# S7CAS-PLEIADES-CARTE-MERE_Pxx_DDR.net
KiCad netlist of a schematic drawn in Altium Designer
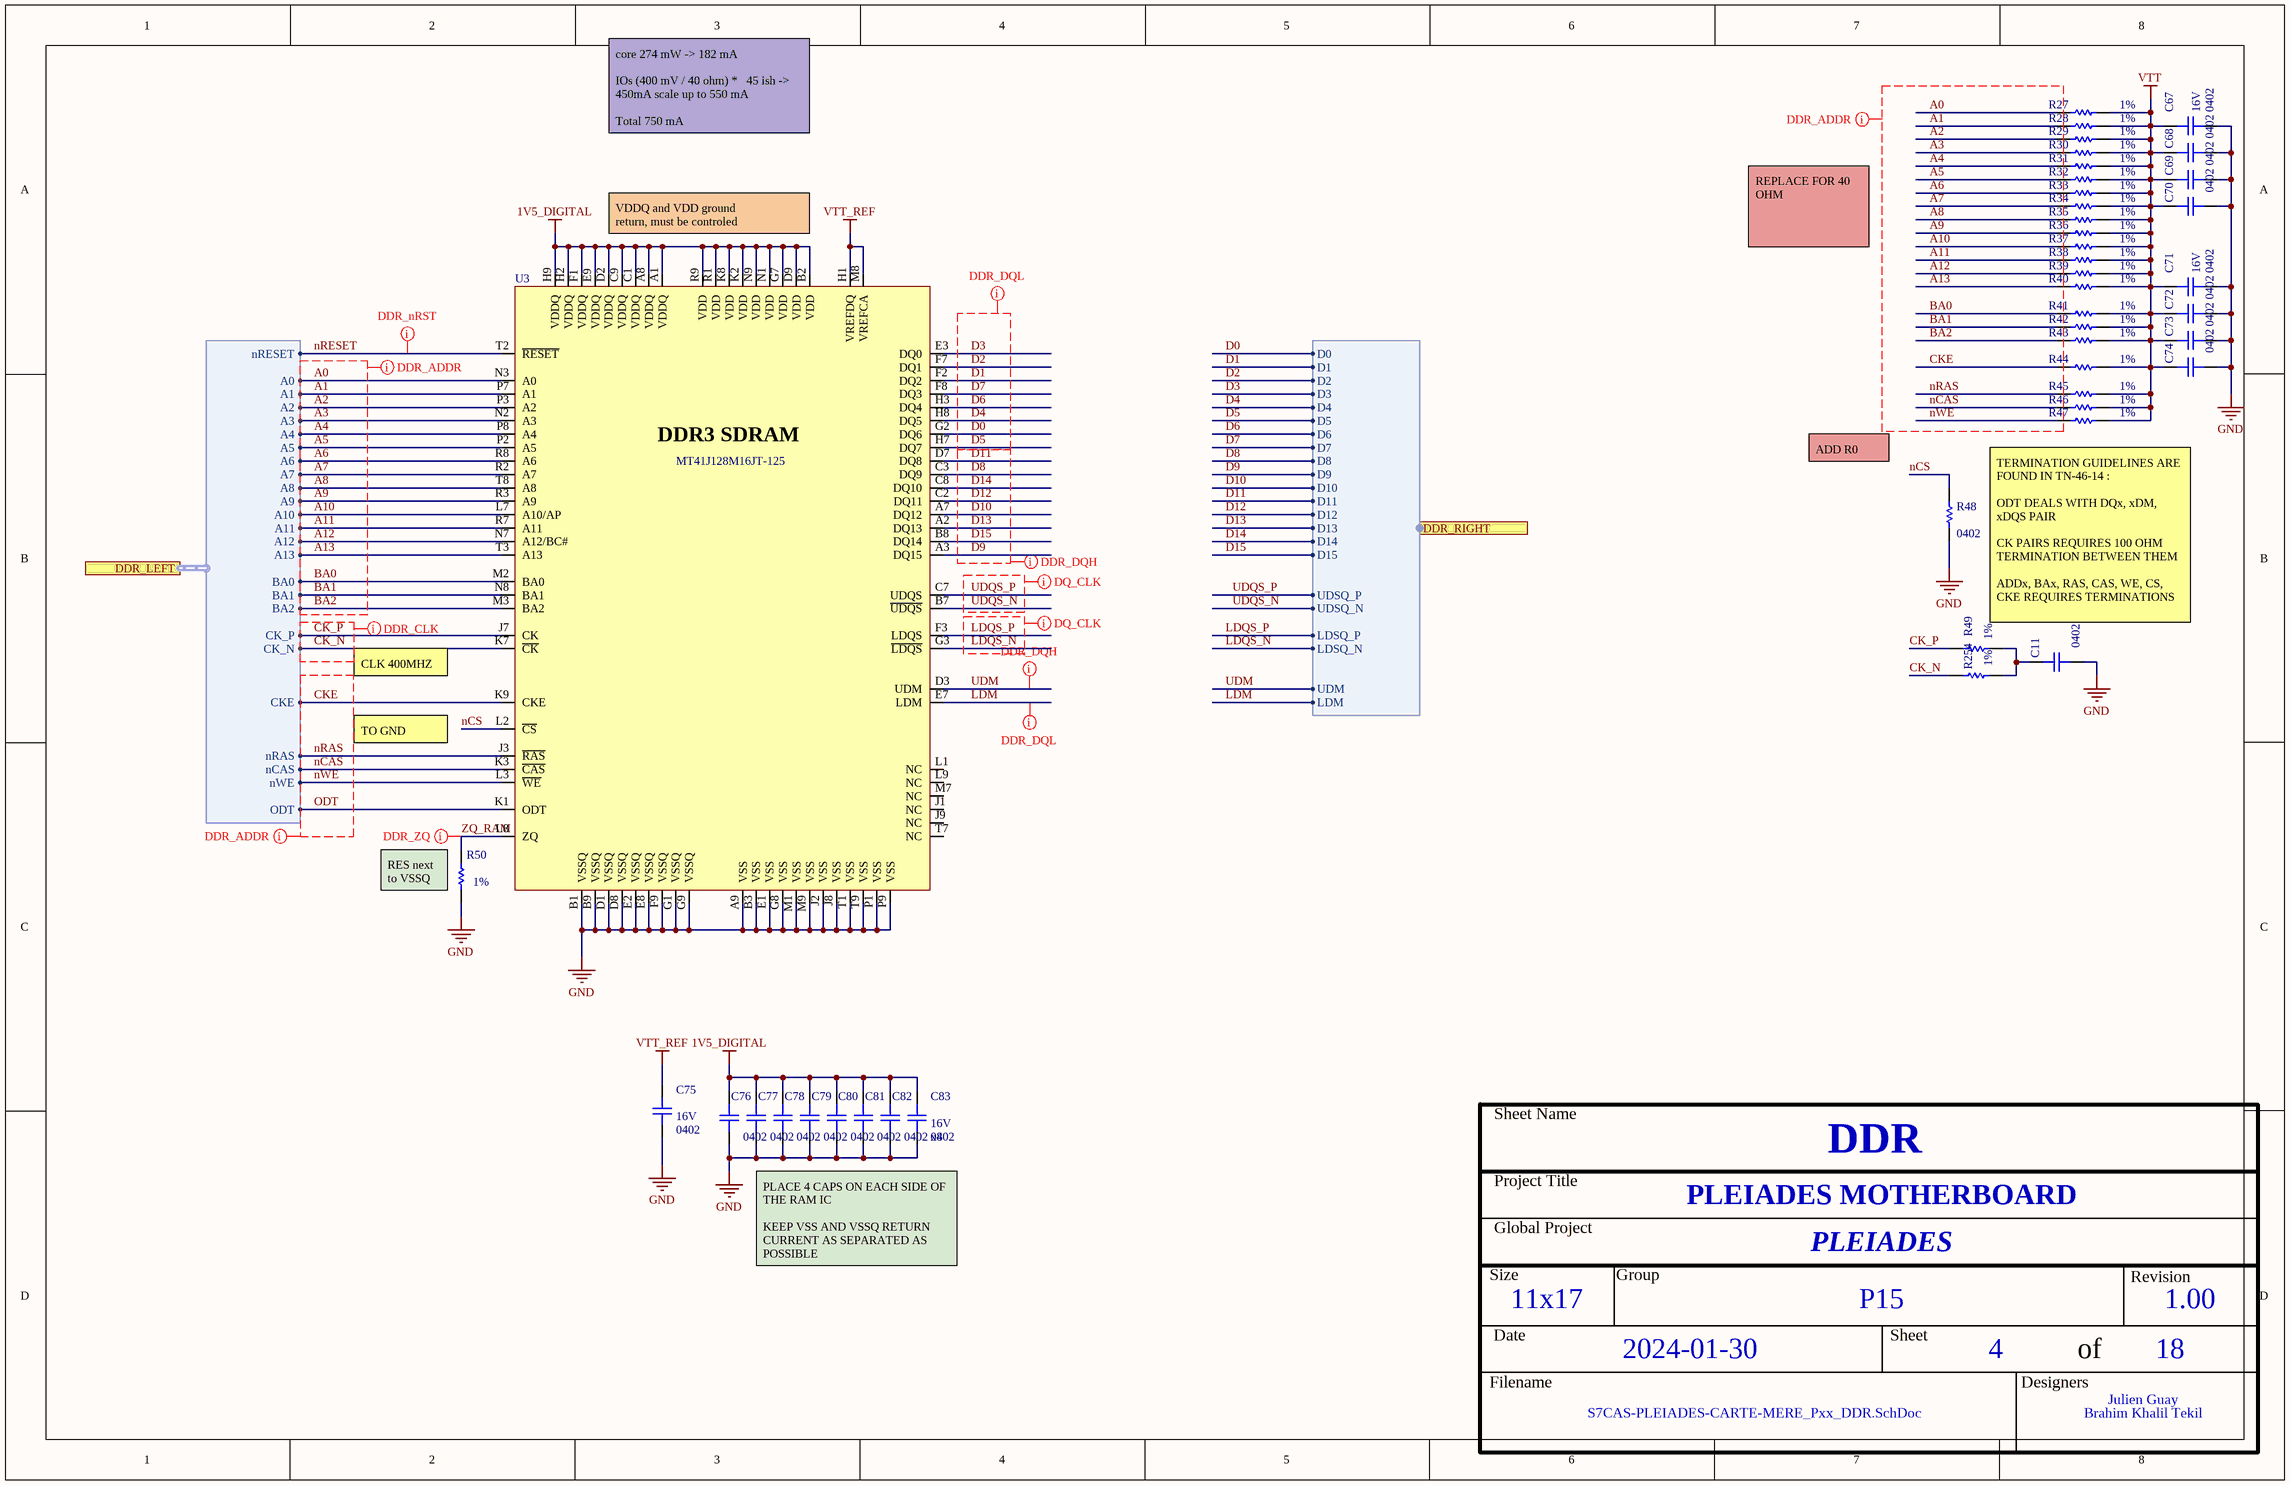
[diagram p0: S7CAS-PLEIADES-CARTE-MERE_Pxx_DDR.SchDoc]

(export (version "E")
  (design (tool "Eeschema 10.0.6"))
  (components
    (comp (ref "C11")
      (value "0402")
      (footprint "S7CAS_LIB2023:CAP_0402")
      (description "CAP - 0402")
      (fields
        (field (name "VOLTAGE") "16V")
        (field (name "PACKAGE") "0402")
        (field (name "CREATEDBY") "Jonathan Bouchard")
      )
      (libsource (lib "S7CAS_LIB2023") (part "CAP - 0603"))
    )
    (comp (ref "C67")
      (value "0402")
      (footprint "S7CAS_LIB2023:CAP_0402")
      (description "CAP - 0402")
      (fields
        (field (name "VOLTAGE") "16V")
        (field (name "PACKAGE") "0402")
        (field (name "CREATEDBY") "Jonathan Bouchard")
      )
      (libsource (lib "S7CAS_LIB2023") (part "CAP - 0603"))
    )
    (comp (ref "C68")
      (value "0402")
      (footprint "S7CAS_LIB2023:CAP_0402")
      (description "CAP - 0402")
      (fields
        (field (name "VOLTAGE") "16V")
        (field (name "PACKAGE") "0402")
        (field (name "CREATEDBY") "Jonathan Bouchard")
      )
      (libsource (lib "S7CAS_LIB2023") (part "CAP - 0603"))
    )
    (comp (ref "C69")
      (value "0402")
      (footprint "S7CAS_LIB2023:CAP_0402")
      (description "CAP - 0402")
      (fields
        (field (name "VOLTAGE") "16V")
        (field (name "PACKAGE") "0402")
        (field (name "CREATEDBY") "Jonathan Bouchard")
      )
      (libsource (lib "S7CAS_LIB2023") (part "CAP - 0603"))
    )
    (comp (ref "C70")
      (value "0402")
      (footprint "S7CAS_LIB2023:CAP_0402")
      (description "CAP - 0402")
      (fields
        (field (name "VOLTAGE") "16V")
        (field (name "PACKAGE") "0402")
        (field (name "CREATEDBY") "Jonathan Bouchard")
      )
      (libsource (lib "S7CAS_LIB2023") (part "CAP - 0603"))
    )
    (comp (ref "C71")
      (value "0402")
      (footprint "S7CAS_LIB2023:CAP_0402")
      (description "CAP - 0402")
      (fields
        (field (name "VOLTAGE") "16V")
        (field (name "PACKAGE") "0402")
        (field (name "CREATEDBY") "Jonathan Bouchard")
      )
      (libsource (lib "S7CAS_LIB2023") (part "CAP - 0603"))
    )
    (comp (ref "C72")
      (value "0402")
      (footprint "S7CAS_LIB2023:CAP_0402")
      (description "CAP - 0402")
      (fields
        (field (name "VOLTAGE") "16V")
        (field (name "PACKAGE") "0402")
        (field (name "CREATEDBY") "Jonathan Bouchard")
      )
      (libsource (lib "S7CAS_LIB2023") (part "CAP - 0603"))
    )
    (comp (ref "C73")
      (value "0402")
      (footprint "S7CAS_LIB2023:CAP_0402")
      (description "CAP - 0402")
      (fields
        (field (name "VOLTAGE") "16V")
        (field (name "PACKAGE") "0402")
        (field (name "CREATEDBY") "Jonathan Bouchard")
      )
      (libsource (lib "S7CAS_LIB2023") (part "CAP - 0603"))
    )
    (comp (ref "C74")
      (value "0402")
      (footprint "S7CAS_LIB2023:CAP_0402")
      (description "CAP - 0402")
      (fields
        (field (name "VOLTAGE") "16V")
        (field (name "PACKAGE") "0402")
        (field (name "CREATEDBY") "Jonathan Bouchard")
      )
      (libsource (lib "S7CAS_LIB2023") (part "CAP - 0603"))
    )
    (comp (ref "C75")
      (value "0402")
      (footprint "S7CAS_LIB2023:CAP_0402")
      (description "CAP - 0402")
      (fields
        (field (name "VOLTAGE") "16V")
        (field (name "PACKAGE") "0402")
        (field (name "CREATEDBY") "Jonathan Bouchard")
      )
      (libsource (lib "S7CAS_LIB2023") (part "CAP - 0603"))
    )
    (comp (ref "C76")
      (value "0402")
      (footprint "S7CAS_LIB2023:CAP_0402")
      (description "CAP - 0402")
      (fields
        (field (name "VOLTAGE") "16V")
        (field (name "PACKAGE") "0402")
        (field (name "CREATEDBY") "Jonathan Bouchard")
      )
      (libsource (lib "S7CAS_LIB2023") (part "CAP - 0603"))
    )
    (comp (ref "C77")
      (value "0402")
      (footprint "S7CAS_LIB2023:CAP_0402")
      (description "CAP - 0402")
      (fields
        (field (name "VOLTAGE") "16V")
        (field (name "PACKAGE") "0402")
        (field (name "CREATEDBY") "Jonathan Bouchard")
      )
      (libsource (lib "S7CAS_LIB2023") (part "CAP - 0603"))
    )
    (comp (ref "C78")
      (value "0402")
      (footprint "S7CAS_LIB2023:CAP_0402")
      (description "CAP - 0402")
      (fields
        (field (name "VOLTAGE") "16V")
        (field (name "PACKAGE") "0402")
        (field (name "CREATEDBY") "Jonathan Bouchard")
      )
      (libsource (lib "S7CAS_LIB2023") (part "CAP - 0603"))
    )
    (comp (ref "C79")
      (value "0402")
      (footprint "S7CAS_LIB2023:CAP_0402")
      (description "CAP - 0402")
      (fields
        (field (name "VOLTAGE") "16V")
        (field (name "PACKAGE") "0402")
        (field (name "CREATEDBY") "Jonathan Bouchard")
      )
      (libsource (lib "S7CAS_LIB2023") (part "CAP - 0603"))
    )
    (comp (ref "C80")
      (value "0402")
      (footprint "S7CAS_LIB2023:CAP_0402")
      (description "CAP - 0402")
      (fields
        (field (name "VOLTAGE") "16V")
        (field (name "PACKAGE") "0402")
        (field (name "CREATEDBY") "Jonathan Bouchard")
      )
      (libsource (lib "S7CAS_LIB2023") (part "CAP - 0603"))
    )
    (comp (ref "C81")
      (value "0402")
      (footprint "S7CAS_LIB2023:CAP_0402")
      (description "CAP - 0402")
      (fields
        (field (name "VOLTAGE") "16V")
        (field (name "PACKAGE") "0402")
        (field (name "CREATEDBY") "Jonathan Bouchard")
      )
      (libsource (lib "S7CAS_LIB2023") (part "CAP - 0603"))
    )
    (comp (ref "C82")
      (value "0402")
      (footprint "S7CAS_LIB2023:CAP_0402")
      (description "CAP - 0402")
      (fields
        (field (name "VOLTAGE") "16V")
        (field (name "PACKAGE") "0402")
        (field (name "CREATEDBY") "Jonathan Bouchard")
      )
      (libsource (lib "S7CAS_LIB2023") (part "CAP - 0603"))
    )
    (comp (ref "C83")
      (value "0402")
      (footprint "S7CAS_LIB2023:CAP_0402")
      (description "CAP - 0402")
      (fields
        (field (name "VOLTAGE") "16V")
        (field (name "PACKAGE") "0402")
        (field (name "CREATEDBY") "Jonathan Bouchard")
      )
      (libsource (lib "S7CAS_LIB2023") (part "CAP - 0603"))
    )
    (comp (ref "R27")
      (value "RES - 0603")
      (footprint "S7CAS_LIB2023:RES_0402")
      (description "RES - 0402")
      (fields (field (name "PRECISION") "1%") (field (name "CREATEDBY") "Jonathan Bouchard"))
      (libsource (lib "S7CAS_LIB2023") (part "RES - 0603"))
    )
    (comp (ref "R28")
      (value "RES - 0603")
      (footprint "S7CAS_LIB2023:RES_0402")
      (description "RES - 0402")
      (fields (field (name "PRECISION") "1%") (field (name "CREATEDBY") "Jonathan Bouchard"))
      (libsource (lib "S7CAS_LIB2023") (part "RES - 0603"))
    )
    (comp (ref "R29")
      (value "RES - 0603")
      (footprint "S7CAS_LIB2023:RES_0402")
      (description "RES - 0402")
      (fields (field (name "PRECISION") "1%") (field (name "CREATEDBY") "Jonathan Bouchard"))
      (libsource (lib "S7CAS_LIB2023") (part "RES - 0603"))
    )
    (comp (ref "R30")
      (value "RES - 0603")
      (footprint "S7CAS_LIB2023:RES_0402")
      (description "RES - 0402")
      (fields (field (name "PRECISION") "1%") (field (name "CREATEDBY") "Jonathan Bouchard"))
      (libsource (lib "S7CAS_LIB2023") (part "RES - 0603"))
    )
    (comp (ref "R31")
      (value "RES - 0603")
      (footprint "S7CAS_LIB2023:RES_0402")
      (description "RES - 0402")
      (fields (field (name "PRECISION") "1%") (field (name "CREATEDBY") "Jonathan Bouchard"))
      (libsource (lib "S7CAS_LIB2023") (part "RES - 0603"))
    )
    (comp (ref "R32")
      (value "RES - 0603")
      (footprint "S7CAS_LIB2023:RES_0402")
      (description "RES - 0402")
      (fields (field (name "PRECISION") "1%") (field (name "CREATEDBY") "Jonathan Bouchard"))
      (libsource (lib "S7CAS_LIB2023") (part "RES - 0603"))
    )
    (comp (ref "R33")
      (value "RES - 0603")
      (footprint "S7CAS_LIB2023:RES_0402")
      (description "RES - 0402")
      (fields (field (name "PRECISION") "1%") (field (name "CREATEDBY") "Jonathan Bouchard"))
      (libsource (lib "S7CAS_LIB2023") (part "RES - 0603"))
    )
    (comp (ref "R34")
      (value "RES - 0603")
      (footprint "S7CAS_LIB2023:RES_0402")
      (description "RES - 0402")
      (fields (field (name "PRECISION") "1%") (field (name "CREATEDBY") "Jonathan Bouchard"))
      (libsource (lib "S7CAS_LIB2023") (part "RES - 0603"))
    )
    (comp (ref "R35")
      (value "RES - 0603")
      (footprint "S7CAS_LIB2023:RES_0402")
      (description "RES - 0402")
      (fields (field (name "PRECISION") "1%") (field (name "CREATEDBY") "Jonathan Bouchard"))
      (libsource (lib "S7CAS_LIB2023") (part "RES - 0603"))
    )
    (comp (ref "R36")
      (value "RES - 0603")
      (footprint "S7CAS_LIB2023:RES_0402")
      (description "RES - 0402")
      (fields (field (name "PRECISION") "1%") (field (name "CREATEDBY") "Jonathan Bouchard"))
      (libsource (lib "S7CAS_LIB2023") (part "RES - 0603"))
    )
    (comp (ref "R37")
      (value "RES - 0603")
      (footprint "S7CAS_LIB2023:RES_0402")
      (description "RES - 0402")
      (fields (field (name "PRECISION") "1%") (field (name "CREATEDBY") "Jonathan Bouchard"))
      (libsource (lib "S7CAS_LIB2023") (part "RES - 0603"))
    )
    (comp (ref "R38")
      (value "RES - 0603")
      (footprint "S7CAS_LIB2023:RES_0402")
      (description "RES - 0402")
      (fields (field (name "PRECISION") "1%") (field (name "CREATEDBY") "Jonathan Bouchard"))
      (libsource (lib "S7CAS_LIB2023") (part "RES - 0603"))
    )
    (comp (ref "R39")
      (value "RES - 0603")
      (footprint "S7CAS_LIB2023:RES_0402")
      (description "RES - 0402")
      (fields (field (name "PRECISION") "1%") (field (name "CREATEDBY") "Jonathan Bouchard"))
      (libsource (lib "S7CAS_LIB2023") (part "RES - 0603"))
    )
    (comp (ref "R40")
      (value "RES - 0603")
      (footprint "S7CAS_LIB2023:RES_0402")
      (description "RES - 0402")
      (fields (field (name "PRECISION") "1%") (field (name "CREATEDBY") "Jonathan Bouchard"))
      (libsource (lib "S7CAS_LIB2023") (part "RES - 0603"))
    )
    (comp (ref "R41")
      (value "RES - 0603")
      (footprint "S7CAS_LIB2023:RES_0402")
      (description "RES - 0402")
      (fields (field (name "PRECISION") "1%") (field (name "CREATEDBY") "Jonathan Bouchard"))
      (libsource (lib "S7CAS_LIB2023") (part "RES - 0603"))
    )
    (comp (ref "R42")
      (value "RES - 0603")
      (footprint "S7CAS_LIB2023:RES_0402")
      (description "RES - 0402")
      (fields (field (name "PRECISION") "1%") (field (name "CREATEDBY") "Jonathan Bouchard"))
      (libsource (lib "S7CAS_LIB2023") (part "RES - 0603"))
    )
    (comp (ref "R43")
      (value "RES - 0603")
      (footprint "S7CAS_LIB2023:RES_0402")
      (description "RES - 0402")
      (fields (field (name "PRECISION") "1%") (field (name "CREATEDBY") "Jonathan Bouchard"))
      (libsource (lib "S7CAS_LIB2023") (part "RES - 0603"))
    )
    (comp (ref "R44")
      (value "RES - 0603")
      (footprint "S7CAS_LIB2023:RES_0402")
      (description "RES - 0402")
      (fields (field (name "PRECISION") "1%") (field (name "CREATEDBY") "Jonathan Bouchard"))
      (libsource (lib "S7CAS_LIB2023") (part "RES - 0603"))
    )
    (comp (ref "R45")
      (value "RES - 0603")
      (footprint "S7CAS_LIB2023:RES_0402")
      (description "RES - 0402")
      (fields (field (name "PRECISION") "1%") (field (name "CREATEDBY") "Jonathan Bouchard"))
      (libsource (lib "S7CAS_LIB2023") (part "RES - 0603"))
    )
    (comp (ref "R46")
      (value "RES - 0603")
      (footprint "S7CAS_LIB2023:RES_0402")
      (description "RES - 0402")
      (fields (field (name "PRECISION") "1%") (field (name "CREATEDBY") "Jonathan Bouchard"))
      (libsource (lib "S7CAS_LIB2023") (part "RES - 0603"))
    )
    (comp (ref "R47")
      (value "RES - 0603")
      (footprint "S7CAS_LIB2023:RES_0402")
      (description "RES - 0402")
      (fields (field (name "PRECISION") "1%") (field (name "CREATEDBY") "Jonathan Bouchard"))
      (libsource (lib "S7CAS_LIB2023") (part "RES - 0603"))
    )
    (comp (ref "R48")
      (value "RES - 0603")
      (footprint "S7CAS_LIB2023:RES_0402")
      (description "RES - 0402")
      (fields (field (name "PACKAGE") "0402") (field (name "CREATEDBY") "Jonathan Bouchard"))
      (libsource (lib "S7CAS_LIB2023") (part "RES - 0603"))
    )
    (comp (ref "R49")
      (value "RES - 0603")
      (footprint "S7CAS_LIB2023:RES_0402")
      (description "RES - 0402")
      (fields (field (name "PRECISION") "1%") (field (name "CREATEDBY") "Jonathan Bouchard"))
      (libsource (lib "S7CAS_LIB2023") (part "RES - 0603"))
    )
    (comp (ref "R50")
      (value "RES - 0603")
      (footprint "S7CAS_LIB2023:RES_0402")
      (description "RES - 0402")
      (fields (field (name "PRECISION") "1%") (field (name "CREATEDBY") "Jonathan Bouchard"))
      (libsource (lib "S7CAS_LIB2023") (part "RES - 0603"))
    )
    (comp (ref "R254")
      (value "RES - 0603")
      (footprint "S7CAS_LIB2023:RES_0402")
      (description "RES - 0402")
      (fields (field (name "PRECISION") "1%") (field (name "CREATEDBY") "Jonathan Bouchard"))
      (libsource (lib "S7CAS_LIB2023") (part "RES - 0603"))
    )
    (comp (ref "U3")
      (value "MT41J128M16JT-125")
      (footprint "MEM_DDR3_MT41J128M16JT-125")
      (description "MEM - DDR3 SDRAM 2GBIT 800MHZ - TFBGA-96")
      (fields
        (field (name "VOLTAGE") "1.425 V ~ 1.575 V")
        (field (name "MFG") "Micrel")
        (field (name "CREATEDBY") "Jonathan Bouchard")
      )
      (libsource (lib "S7CAS_LIB2023") (part "MEM_DDR3_MT41J128M16JT-125{colon}K TR"))
    )
  )
  (nets
    (net (code "3") (name "/A0") (class "Default")
      (node (ref "R27") (pin "2") (pinfunction "2_2") (pintype "passive"))
      (node (ref "U3") (pin "N3") (pinfunction "A0_N3") (pintype "passive"))
    )
    (net (code "4") (name "/A1") (class "Default")
      (node (ref "R28") (pin "2") (pinfunction "2_2") (pintype "passive"))
      (node (ref "U3") (pin "P7") (pinfunction "A1_P7") (pintype "passive"))
    )
    (net (code "5") (name "/A2") (class "Default")
      (node (ref "R29") (pin "2") (pinfunction "2_2") (pintype "passive"))
      (node (ref "U3") (pin "P3") (pinfunction "A2_P3") (pintype "passive"))
    )
    (net (code "6") (name "/A3") (class "Default")
      (node (ref "R30") (pin "2") (pinfunction "2_2") (pintype "passive"))
      (node (ref "U3") (pin "N2") (pinfunction "A3_N2") (pintype "passive"))
    )
    (net (code "7") (name "/A4") (class "Default")
      (node (ref "R31") (pin "2") (pinfunction "2_2") (pintype "passive"))
      (node (ref "U3") (pin "P8") (pinfunction "A4_P8") (pintype "passive"))
    )
    (net (code "8") (name "/A5") (class "Default")
      (node (ref "R32") (pin "2") (pinfunction "2_2") (pintype "passive"))
      (node (ref "U3") (pin "P2") (pinfunction "A5_P2") (pintype "passive"))
    )
    (net (code "9") (name "/A6") (class "Default")
      (node (ref "R33") (pin "2") (pinfunction "2_2") (pintype "passive"))
      (node (ref "U3") (pin "R8") (pinfunction "A6_R8") (pintype "passive"))
    )
    (net (code "10") (name "/A7") (class "Default")
      (node (ref "R34") (pin "2") (pinfunction "2_2") (pintype "passive"))
      (node (ref "U3") (pin "R2") (pinfunction "A7_R2") (pintype "passive"))
    )
    (net (code "11") (name "/A8") (class "Default")
      (node (ref "R35") (pin "2") (pinfunction "2_2") (pintype "passive"))
      (node (ref "U3") (pin "T8") (pinfunction "A8_T8") (pintype "passive"))
    )
    (net (code "12") (name "/A9") (class "Default")
      (node (ref "R36") (pin "2") (pinfunction "2_2") (pintype "passive"))
      (node (ref "U3") (pin "R3") (pinfunction "A9_R3") (pintype "passive"))
    )
    (net (code "13") (name "/A10") (class "Default")
      (node (ref "R37") (pin "2") (pinfunction "2_2") (pintype "passive"))
      (node (ref "U3") (pin "L7") (pinfunction "A10/AP_L7") (pintype "passive"))
    )
    (net (code "14") (name "/A11") (class "Default")
      (node (ref "R38") (pin "2") (pinfunction "2_2") (pintype "passive"))
      (node (ref "U3") (pin "R7") (pinfunction "A11_R7") (pintype "passive"))
    )
    (net (code "15") (name "/A12") (class "Default")
      (node (ref "R39") (pin "2") (pinfunction "2_2") (pintype "passive"))
      (node (ref "U3") (pin "N7") (pinfunction "A12/BC#_N7") (pintype "passive"))
    )
    (net (code "16") (name "/A13") (class "Default")
      (node (ref "R40") (pin "2") (pinfunction "2_2") (pintype "passive"))
      (node (ref "U3") (pin "T3") (pinfunction "A13_T3") (pintype "passive"))
    )
    (net (code "17") (name "/BA0") (class "Default")
      (node (ref "R41") (pin "2") (pinfunction "2_2") (pintype "passive"))
      (node (ref "U3") (pin "M2") (pinfunction "BA0_M2") (pintype "passive"))
    )
    (net (code "18") (name "/BA1") (class "Default")
      (node (ref "R42") (pin "2") (pinfunction "2_2") (pintype "passive"))
      (node (ref "U3") (pin "N8") (pinfunction "BA1_N8") (pintype "passive"))
    )
    (net (code "19") (name "/BA2") (class "Default")
      (node (ref "R43") (pin "2") (pinfunction "2_2") (pintype "passive"))
      (node (ref "U3") (pin "M3") (pinfunction "BA2_M3") (pintype "passive"))
    )
    (net (code "20") (name "/CKE") (class "Default")
      (node (ref "R44") (pin "2") (pinfunction "2_2") (pintype "passive"))
      (node (ref "U3") (pin "K9") (pinfunction "CKE_K9") (pintype "passive"))
    )
    (net (code "21") (name "/CK_N") (class "Default")
      (node (ref "R254") (pin "2") (pinfunction "2_2") (pintype "passive"))
      (node (ref "U3") (pin "K7") (pinfunction "CK_K7") (pintype "passive"))
    )
    (net (code "22") (name "/CK_P") (class "Default")
      (node (ref "R49") (pin "2") (pinfunction "2_2") (pintype "passive"))
      (node (ref "U3") (pin "J7") (pinfunction "CK_J7") (pintype "passive"))
    )
    (net (code "23") (name "/D0") (class "Default")
      (node (ref "U3") (pin "G2") (pinfunction "DQ6_G2") (pintype "passive"))
    )
    (net (code "24") (name "/D1") (class "Default")
      (node (ref "U3") (pin "F2") (pinfunction "DQ2_F2") (pintype "passive"))
    )
    (net (code "25") (name "/D2") (class "Default")
      (node (ref "U3") (pin "F7") (pinfunction "DQ1_F7") (pintype "passive"))
    )
    (net (code "26") (name "/D3") (class "Default")
      (node (ref "U3") (pin "E3") (pinfunction "DQ0_E3") (pintype "passive"))
    )
    (net (code "27") (name "/D4") (class "Default")
      (node (ref "U3") (pin "H8") (pinfunction "DQ5_H8") (pintype "passive"))
    )
    (net (code "28") (name "/D5") (class "Default")
      (node (ref "U3") (pin "H7") (pinfunction "DQ7_H7") (pintype "passive"))
    )
    (net (code "29") (name "/D6") (class "Default")
      (node (ref "U3") (pin "H3") (pinfunction "DQ4_H3") (pintype "passive"))
    )
    (net (code "30") (name "/D7") (class "Default")
      (node (ref "U3") (pin "F8") (pinfunction "DQ3_F8") (pintype "passive"))
    )
    (net (code "31") (name "/D8") (class "Default")
      (node (ref "U3") (pin "C3") (pinfunction "DQ9_C3") (pintype "passive"))
    )
    (net (code "32") (name "/D9") (class "Default")
      (node (ref "U3") (pin "A3") (pinfunction "DQ15_A3") (pintype "passive"))
    )
    (net (code "33") (name "/D10") (class "Default")
      (node (ref "U3") (pin "A7") (pinfunction "DQ12_A7") (pintype "passive"))
    )
    (net (code "34") (name "/D11") (class "Default")
      (node (ref "U3") (pin "D7") (pinfunction "DQ8_D7") (pintype "passive"))
    )
    (net (code "35") (name "/D12") (class "Default")
      (node (ref "U3") (pin "C2") (pinfunction "DQ11_C2") (pintype "passive"))
    )
    (net (code "36") (name "/D13") (class "Default")
      (node (ref "U3") (pin "A2") (pinfunction "DQ13_A2") (pintype "passive"))
    )
    (net (code "37") (name "/D14") (class "Default")
      (node (ref "U3") (pin "C8") (pinfunction "DQ10_C8") (pintype "passive"))
    )
    (net (code "38") (name "/D15") (class "Default")
      (node (ref "U3") (pin "B8") (pinfunction "DQ14_B8") (pintype "passive"))
    )
    (net (code "39") (name "/LDM") (class "Default")
      (node (ref "U3") (pin "E7") (pinfunction "LDM_E7") (pintype "passive"))
    )
    (net (code "40") (name "/LDQS_N") (class "Default")
      (node (ref "U3") (pin "G3") (pinfunction "LDQS_G3") (pintype "passive"))
    )
    (net (code "41") (name "/LDQS_P") (class "Default")
      (node (ref "U3") (pin "F3") (pinfunction "LDQS_F3") (pintype "passive"))
    )
    (net (code "42") (name "/ODT") (class "Default")
      (node (ref "U3") (pin "K1") (pinfunction "ODT_K1") (pintype "passive"))
    )
    (net (code "43") (name "/UDM") (class "Default")
      (node (ref "U3") (pin "D3") (pinfunction "UDM_D3") (pintype "passive"))
    )
    (net (code "44") (name "/UDQS_N") (class "Default")
      (node (ref "U3") (pin "B7") (pinfunction "UDQS_B7") (pintype "passive"))
    )
    (net (code "45") (name "/UDQS_P") (class "Default")
      (node (ref "U3") (pin "C7") (pinfunction "UDQS_C7") (pintype "passive"))
    )
    (net (code "46") (name "/ZQ_RAM") (class "Default")
      (node (ref "R50") (pin "2") (pinfunction "2_2") (pintype "passive"))
      (node (ref "U3") (pin "L8") (pinfunction "ZQ_L8") (pintype "passive"))
    )
    (net (code "47") (name "/nCAS") (class "Default")
      (node (ref "R46") (pin "2") (pinfunction "2_2") (pintype "passive"))
      (node (ref "U3") (pin "K3") (pinfunction "CAS_K3") (pintype "passive"))
    )
    (net (code "48") (name "/nCS") (class "Default")
      (node (ref "R48") (pin "2") (pinfunction "2_2") (pintype "passive"))
      (node (ref "U3") (pin "L2") (pinfunction "CS_L2") (pintype "passive"))
    )
    (net (code "49") (name "/nRAS") (class "Default")
      (node (ref "R45") (pin "2") (pinfunction "2_2") (pintype "passive"))
      (node (ref "U3") (pin "J3") (pinfunction "RAS_J3") (pintype "passive"))
    )
    (net (code "50") (name "/nRESET") (class "Default")
      (node (ref "U3") (pin "T2") (pinfunction "RESET_T2") (pintype "passive"))
    )
    (net (code "51") (name "/nWE") (class "Default")
      (node (ref "R47") (pin "2") (pinfunction "2_2") (pintype "passive"))
      (node (ref "U3") (pin "L3") (pinfunction "WE_L3") (pintype "passive"))
    )
    (net (code "54") (name "1V5_DIGITAL") (class "Default")
      (node (ref "C76") (pin "2") (pinfunction "2_2") (pintype "passive"))
      (node (ref "C77") (pin "2") (pinfunction "2_2") (pintype "passive"))
      (node (ref "C78") (pin "2") (pinfunction "2_2") (pintype "passive"))
      (node (ref "C79") (pin "2") (pinfunction "2_2") (pintype "passive"))
      (node (ref "C80") (pin "2") (pinfunction "2_2") (pintype "passive"))
      (node (ref "C81") (pin "2") (pinfunction "2_2") (pintype "passive"))
      (node (ref "C82") (pin "2") (pinfunction "2_2") (pintype "passive"))
      (node (ref "C83") (pin "2") (pinfunction "2_2") (pintype "passive"))
      (node (ref "U3") (pin "A1") (pinfunction "VDDQ_A1") (pintype "passive"))
      (node (ref "U3") (pin "A8") (pinfunction "VDDQ_A8") (pintype "passive"))
      (node (ref "U3") (pin "B2") (pinfunction "VDD_B2") (pintype "passive"))
      (node (ref "U3") (pin "C1") (pinfunction "VDDQ_C1") (pintype "passive"))
      (node (ref "U3") (pin "C9") (pinfunction "VDDQ_C9") (pintype "passive"))
      (node (ref "U3") (pin "D2") (pinfunction "VDDQ_D2") (pintype "passive"))
      (node (ref "U3") (pin "D9") (pinfunction "VDD_D9") (pintype "passive"))
      (node (ref "U3") (pin "E9") (pinfunction "VDDQ_E9") (pintype "passive"))
      (node (ref "U3") (pin "F1") (pinfunction "VDDQ_F1") (pintype "passive"))
      (node (ref "U3") (pin "G7") (pinfunction "VDD_G7") (pintype "passive"))
      (node (ref "U3") (pin "H2") (pinfunction "VDDQ_H2") (pintype "passive"))
      (node (ref "U3") (pin "H9") (pinfunction "VDDQ_H9") (pintype "passive"))
      (node (ref "U3") (pin "K2") (pinfunction "VDD_K2") (pintype "passive"))
      (node (ref "U3") (pin "K8") (pinfunction "VDD_K8") (pintype "passive"))
      (node (ref "U3") (pin "N1") (pinfunction "VDD_N1") (pintype "passive"))
      (node (ref "U3") (pin "N9") (pinfunction "VDD_N9") (pintype "passive"))
      (node (ref "U3") (pin "R1") (pinfunction "VDD_R1") (pintype "passive"))
      (node (ref "U3") (pin "R9") (pinfunction "VDD_R9") (pintype "passive"))
    )
    (net (code "55") (name "GND") (class "Default")
      (node (ref "C11") (pin "1") (pinfunction "1_1") (pintype "passive"))
      (node (ref "C67") (pin "1") (pinfunction "1_1") (pintype "passive"))
      (node (ref "C68") (pin "1") (pinfunction "1_1") (pintype "passive"))
      (node (ref "C69") (pin "1") (pinfunction "1_1") (pintype "passive"))
      (node (ref "C70") (pin "1") (pinfunction "1_1") (pintype "passive"))
      (node (ref "C71") (pin "1") (pinfunction "1_1") (pintype "passive"))
      (node (ref "C72") (pin "1") (pinfunction "1_1") (pintype "passive"))
      (node (ref "C73") (pin "1") (pinfunction "1_1") (pintype "passive"))
      (node (ref "C74") (pin "1") (pinfunction "1_1") (pintype "passive"))
      (node (ref "C75") (pin "1") (pinfunction "1_1") (pintype "passive"))
      (node (ref "C76") (pin "1") (pinfunction "1_1") (pintype "passive"))
      (node (ref "C77") (pin "1") (pinfunction "1_1") (pintype "passive"))
      (node (ref "C78") (pin "1") (pinfunction "1_1") (pintype "passive"))
      (node (ref "C79") (pin "1") (pinfunction "1_1") (pintype "passive"))
      (node (ref "C80") (pin "1") (pinfunction "1_1") (pintype "passive"))
      (node (ref "C81") (pin "1") (pinfunction "1_1") (pintype "passive"))
      (node (ref "C82") (pin "1") (pinfunction "1_1") (pintype "passive"))
      (node (ref "C83") (pin "1") (pinfunction "1_1") (pintype "passive"))
      (node (ref "R48") (pin "1") (pinfunction "1_1") (pintype "passive"))
      (node (ref "R50") (pin "1") (pinfunction "1_1") (pintype "passive"))
      (node (ref "U3") (pin "A9") (pinfunction "VSS_A9") (pintype "passive"))
      (node (ref "U3") (pin "B1") (pinfunction "VSSQ_B1") (pintype "passive"))
      (node (ref "U3") (pin "B3") (pinfunction "VSS_B3") (pintype "passive"))
      (node (ref "U3") (pin "B9") (pinfunction "VSSQ_B9") (pintype "passive"))
      (node (ref "U3") (pin "D1") (pinfunction "VSSQ_D1") (pintype "passive"))
      (node (ref "U3") (pin "D8") (pinfunction "VSSQ_D8") (pintype "passive"))
      (node (ref "U3") (pin "E1") (pinfunction "VSS_E1") (pintype "passive"))
      (node (ref "U3") (pin "E2") (pinfunction "VSSQ_E2") (pintype "passive"))
      (node (ref "U3") (pin "E8") (pinfunction "VSSQ_E8") (pintype "passive"))
      (node (ref "U3") (pin "F9") (pinfunction "VSSQ_F9") (pintype "passive"))
      (node (ref "U3") (pin "G1") (pinfunction "VSSQ_G1") (pintype "passive"))
      (node (ref "U3") (pin "G8") (pinfunction "VSS_G8") (pintype "passive"))
      (node (ref "U3") (pin "G9") (pinfunction "VSSQ_G9") (pintype "passive"))
      (node (ref "U3") (pin "J2") (pinfunction "VSS_J2") (pintype "passive"))
      (node (ref "U3") (pin "J8") (pinfunction "VSS_J8") (pintype "passive"))
      (node (ref "U3") (pin "M1") (pinfunction "VSS_M1") (pintype "passive"))
      (node (ref "U3") (pin "M9") (pinfunction "VSS_M9") (pintype "passive"))
      (node (ref "U3") (pin "P1") (pinfunction "VSS_P1") (pintype "passive"))
      (node (ref "U3") (pin "P9") (pinfunction "VSS_P9") (pintype "passive"))
      (node (ref "U3") (pin "T1") (pinfunction "VSS_T1") (pintype "passive"))
      (node (ref "U3") (pin "T9") (pinfunction "VSS_T9") (pintype "passive"))
    )
    (net (code "56") (name "Net-(C11-Pad2)") (class "Default")
      (node (ref "C11") (pin "2") (pinfunction "2_2") (pintype "passive"))
      (node (ref "R254") (pin "1") (pinfunction "1_1") (pintype "passive"))
      (node (ref "R49") (pin "1") (pinfunction "1_1") (pintype "passive"))
    )
    (net (code "57") (name "VTT") (class "Default")
      (node (ref "C67") (pin "2") (pinfunction "2_2") (pintype "passive"))
      (node (ref "C68") (pin "2") (pinfunction "2_2") (pintype "passive"))
      (node (ref "C69") (pin "2") (pinfunction "2_2") (pintype "passive"))
      (node (ref "C70") (pin "2") (pinfunction "2_2") (pintype "passive"))
      (node (ref "C71") (pin "2") (pinfunction "2_2") (pintype "passive"))
      (node (ref "C72") (pin "2") (pinfunction "2_2") (pintype "passive"))
      (node (ref "C73") (pin "2") (pinfunction "2_2") (pintype "passive"))
      (node (ref "C74") (pin "2") (pinfunction "2_2") (pintype "passive"))
      (node (ref "R27") (pin "1") (pinfunction "1_1") (pintype "passive"))
      (node (ref "R28") (pin "1") (pinfunction "1_1") (pintype "passive"))
      (node (ref "R29") (pin "1") (pinfunction "1_1") (pintype "passive"))
      (node (ref "R30") (pin "1") (pinfunction "1_1") (pintype "passive"))
      (node (ref "R31") (pin "1") (pinfunction "1_1") (pintype "passive"))
      (node (ref "R32") (pin "1") (pinfunction "1_1") (pintype "passive"))
      (node (ref "R33") (pin "1") (pinfunction "1_1") (pintype "passive"))
      (node (ref "R34") (pin "1") (pinfunction "1_1") (pintype "passive"))
      (node (ref "R35") (pin "1") (pinfunction "1_1") (pintype "passive"))
      (node (ref "R36") (pin "1") (pinfunction "1_1") (pintype "passive"))
      (node (ref "R37") (pin "1") (pinfunction "1_1") (pintype "passive"))
      (node (ref "R38") (pin "1") (pinfunction "1_1") (pintype "passive"))
      (node (ref "R39") (pin "1") (pinfunction "1_1") (pintype "passive"))
      (node (ref "R40") (pin "1") (pinfunction "1_1") (pintype "passive"))
      (node (ref "R41") (pin "1") (pinfunction "1_1") (pintype "passive"))
      (node (ref "R42") (pin "1") (pinfunction "1_1") (pintype "passive"))
      (node (ref "R43") (pin "1") (pinfunction "1_1") (pintype "passive"))
      (node (ref "R44") (pin "1") (pinfunction "1_1") (pintype "passive"))
      (node (ref "R45") (pin "1") (pinfunction "1_1") (pintype "passive"))
      (node (ref "R46") (pin "1") (pinfunction "1_1") (pintype "passive"))
      (node (ref "R47") (pin "1") (pinfunction "1_1") (pintype "passive"))
    )
    (net (code "58") (name "VTT_REF") (class "Default")
      (node (ref "C75") (pin "2") (pinfunction "2_2") (pintype "passive"))
      (node (ref "U3") (pin "H1") (pinfunction "VREFDQ_H1") (pintype "passive"))
      (node (ref "U3") (pin "M8") (pinfunction "VREFCA_M8") (pintype "passive"))
    )
    (net (code "59") (name "unconnected-(U3-NC-PadJ1)") (class "Default")
      (node (ref "U3") (pin "J1") (pinfunction "NC_J1") (pintype "passive"))
    )
    (net (code "60") (name "unconnected-(U3-NC-PadJ9)") (class "Default")
      (node (ref "U3") (pin "J9") (pinfunction "NC_J9") (pintype "passive"))
    )
    (net (code "61") (name "unconnected-(U3-NC-PadL1)") (class "Default")
      (node (ref "U3") (pin "L1") (pinfunction "NC_L1") (pintype "passive"))
    )
    (net (code "62") (name "unconnected-(U3-NC-PadL9)") (class "Default")
      (node (ref "U3") (pin "L9") (pinfunction "NC_L9") (pintype "passive"))
    )
    (net (code "63") (name "unconnected-(U3-NC-PadM7)") (class "Default")
      (node (ref "U3") (pin "M7") (pinfunction "NC_M7") (pintype "passive"))
    )
    (net (code "64") (name "unconnected-(U3-NC-PadT7)") (class "Default")
      (node (ref "U3") (pin "T7") (pinfunction "NC_T7") (pintype "passive"))
    )
  )
)
